# XMC4800-Power.net
KiCad netlist of a schematic drawn in Altium Designer
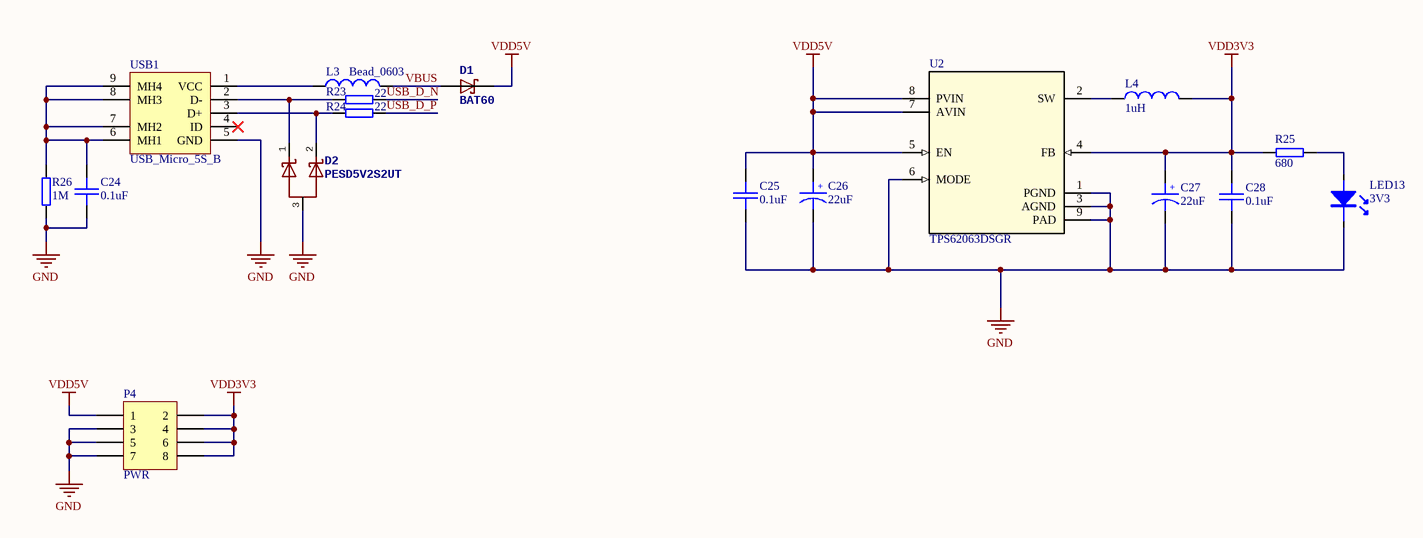
[diagram p0: XMC4800-Power.SchDoc]

(export (version "E")
  (design (tool "Eeschema 10.0.6"))
  (components
    (comp (ref "C24")
      (value "0.1uF")
      (footprint "CAP-0603")
      (description "陶瓷贴片电容0603")
      (fields (field (name "TOLERANCE") "10%") (field (name "VOLTAGE") "50V"))
      (libsource (lib "momo") (part "C_0603"))
    )
    (comp (ref "C25")
      (value "0.1uF")
      (footprint "CAP-0603")
      (description "陶瓷贴片电容0603")
      (fields (field (name "TOLERANCE") "10%") (field (name "VOLTAGE") "50V"))
      (libsource (lib "momo") (part "C_0603"))
    )
    (comp (ref "C26")
      (value "22uF")
      (footprint "C_Tantalum_B")
      (description "贴片钽电容B型")
      (fields (field (name "VOLTAGE") "16V"))
      (libsource (lib "momo") (part "C_Tantalum_B"))
    )
    (comp (ref "C27")
      (value "22uF")
      (footprint "C_Tantalum_B")
      (description "贴片钽电容B型")
      (fields (field (name "VOLTAGE") "16V"))
      (libsource (lib "momo") (part "C_Tantalum_B"))
    )
    (comp (ref "C28")
      (value "0.1uF")
      (footprint "CAP-0603")
      (description "陶瓷贴片电容0603")
      (fields (field (name "TOLERANCE") "10%") (field (name "VOLTAGE") "50V"))
      (libsource (lib "momo") (part "C_0603"))
    )
    (comp (ref "D1")
      (value "BAT60")
      (footprint "LC-SOD-323")
      (description "肖特基二极管")
      (libsource (lib "momo") (part "BAT60"))
    )
    (comp (ref "D2")
      (value "PESD5V2S2UT")
      (footprint "LC-SOT-23-3")
      (libsource (lib "momo") (part "PESD5V2S2UT"))
    )
    (comp (ref "L3")
      (value "Bead_0603")
      (footprint "L-0603")
      (description "贴片磁珠0603")
      (libsource (lib "momo") (part "Bead_0603"))
    )
    (comp (ref "L4")
      (value "1uH")
      (footprint "L-PWR-06030")
      (description "功率电感")
      (fields (field (name "TOLERANCE") "20%"))
      (libsource (lib "momo") (part "L_Power"))
    )
    (comp (ref "LED13")
      (value "3V3")
      (footprint "LED_0603")
      (description "0603封装发光二极管")
      (libsource (lib "momo") (part "LED_0603"))
    )
    (comp (ref "P4")
      (value "PWR")
      (footprint "HDR2X4")
      (description "Header, 4-Pin, Dual row")
      (fields (field (name "PUBLISHER") "Altium Limited"))
      (libsource (lib "Miscellaneous Connectors") (part "Header 4X2"))
    )
    (comp (ref "R23")
      (value "22")
      (footprint "RES-0603")
      (description "贴片电阻0603")
      (fields (field (name "TOLERANCE") "5%") (field (name "VOLTAGE") "50V"))
      (libsource (lib "momo") (part "R_0603"))
    )
    (comp (ref "R24")
      (value "22")
      (footprint "RES-0603")
      (description "贴片电阻0603")
      (fields (field (name "TOLERANCE") "5%") (field (name "VOLTAGE") "50V"))
      (libsource (lib "momo") (part "R_0603"))
    )
    (comp (ref "R25")
      (value "680")
      (footprint "RES-0603")
      (description "贴片电阻0603")
      (fields (field (name "TOLERANCE") "5%") (field (name "VOLTAGE") "50V"))
      (libsource (lib "momo") (part "R_0603"))
    )
    (comp (ref "R26")
      (value "1M")
      (footprint "RES-0603")
      (description "贴片电阻0603")
      (fields (field (name "TOLERANCE") "5%") (field (name "VOLTAGE") "50V"))
      (libsource (lib "momo") (part "R_0603"))
    )
    (comp (ref "U2")
      (value "TPS62063DSGR")
      (footprint "DSG0008A")
      (fields (field (name "PARTNUMBER") "TPS62063DSG") (field (name "MANUFACTURER") "Texas Instruments"))
      (libsource (lib "momo") (part "TPS62063DSGR"))
    )
    (comp (ref "USB1")
      (value "USB_Micro_5S_B")
      (footprint "USB_MICRO_5S_B")
      (description "micro USB母座5SB型")
      (libsource (lib "momo") (part "USB_Micro_5S_B"))
    )
  )
  (nets
    (net (code "1") (name "/USB_D_N") (class "Default")
      (node (ref "R23") (pin "2") (pinfunction "2_2") (pintype "passive"))
    )
    (net (code "2") (name "/USB_D_P") (class "Default")
      (node (ref "R24") (pin "2") (pinfunction "2_2") (pintype "passive"))
    )
    (net (code "3") (name "/VBUS") (class "Default")
      (node (ref "D1") (pin "1") (pinfunction "A_1") (pintype "passive"))
      (node (ref "L3") (pin "2") (pinfunction "2_2") (pintype "passive"))
    )
    (net (code "4") (name "GND") (class "Default")
      (node (ref "C24") (pin "2") (pinfunction "2_2") (pintype "passive"))
      (node (ref "C25") (pin "2") (pinfunction "2_2") (pintype "passive"))
      (node (ref "C26") (pin "2") (pinfunction "2_2") (pintype "passive"))
      (node (ref "C27") (pin "2") (pinfunction "2_2") (pintype "passive"))
      (node (ref "C28") (pin "2") (pinfunction "2_2") (pintype "passive"))
      (node (ref "D2") (pin "3") (pinfunction "3_3") (pintype "passive"))
      (node (ref "LED13") (pin "2") (pinfunction "K_2") (pintype "passive"))
      (node (ref "P4") (pin "3") (pinfunction "3_3") (pintype "passive"))
      (node (ref "P4") (pin "5") (pinfunction "5_5") (pintype "passive"))
      (node (ref "P4") (pin "7") (pinfunction "7_7") (pintype "passive"))
      (node (ref "R26") (pin "1") (pinfunction "1_1") (pintype "passive"))
      (node (ref "U2") (pin "1") (pinfunction "PGND_1") (pintype "power_in"))
      (node (ref "U2") (pin "3") (pinfunction "AGND_3") (pintype "power_in"))
      (node (ref "U2") (pin "6") (pinfunction "MODE_6") (pintype "input"))
      (node (ref "U2") (pin "9") (pinfunction "PAD_9") (pintype "power_in"))
      (node (ref "USB1") (pin "5") (pinfunction "GND_5") (pintype "power_in"))
    )
    (net (code "5") (name "Net-(LED13-A)") (class "Default")
      (node (ref "LED13") (pin "1") (pinfunction "A_1") (pintype "passive"))
      (node (ref "R25") (pin "2") (pinfunction "2_2") (pintype "passive"))
    )
    (net (code "6") (name "Net-(U2-SW)") (class "Default")
      (node (ref "L4") (pin "1") (pinfunction "1_1") (pintype "passive"))
      (node (ref "U2") (pin "2") (pinfunction "SW_2") (pintype "power_in"))
    )
    (net (code "7") (name "Net-(USB1-D+)") (class "Default")
      (node (ref "D2") (pin "2") (pinfunction "2_2") (pintype "passive"))
      (node (ref "R24") (pin "1") (pinfunction "1_1") (pintype "passive"))
      (node (ref "USB1") (pin "3") (pinfunction "D+_3") (pintype "passive"))
    )
    (net (code "8") (name "Net-(USB1-D-)") (class "Default")
      (node (ref "D2") (pin "1") (pinfunction "1_1") (pintype "passive"))
      (node (ref "R23") (pin "1") (pinfunction "1_1") (pintype "passive"))
      (node (ref "USB1") (pin "2") (pinfunction "D-_2") (pintype "passive"))
    )
    (net (code "9") (name "Net-(USB1-MH1)") (class "Default")
      (node (ref "C24") (pin "1") (pinfunction "1_1") (pintype "passive"))
      (node (ref "R26") (pin "2") (pinfunction "2_2") (pintype "passive"))
      (node (ref "USB1") (pin "6") (pinfunction "MH1_6") (pintype "passive"))
      (node (ref "USB1") (pin "7") (pinfunction "MH2_7") (pintype "passive"))
      (node (ref "USB1") (pin "8") (pinfunction "MH3_8") (pintype "passive"))
      (node (ref "USB1") (pin "9") (pinfunction "MH4_9") (pintype "passive"))
    )
    (net (code "10") (name "Net-(USB1-VCC)") (class "Default")
      (node (ref "L3") (pin "1") (pinfunction "1_1") (pintype "passive"))
      (node (ref "USB1") (pin "1") (pinfunction "VCC_1") (pintype "power_in"))
    )
    (net (code "11") (name "VDD3V3") (class "Default")
      (node (ref "C27") (pin "1") (pinfunction "1_1") (pintype "passive"))
      (node (ref "C28") (pin "1") (pinfunction "1_1") (pintype "passive"))
      (node (ref "L4") (pin "2") (pinfunction "2_2") (pintype "passive"))
      (node (ref "P4") (pin "2") (pinfunction "2_2") (pintype "passive"))
      (node (ref "P4") (pin "4") (pinfunction "4_4") (pintype "passive"))
      (node (ref "P4") (pin "6") (pinfunction "6_6") (pintype "passive"))
      (node (ref "P4") (pin "8") (pinfunction "8_8") (pintype "passive"))
      (node (ref "R25") (pin "1") (pinfunction "1_1") (pintype "passive"))
      (node (ref "U2") (pin "4") (pinfunction "FB_4") (pintype "input"))
    )
    (net (code "12") (name "VDD5V") (class "Default")
      (node (ref "C25") (pin "1") (pinfunction "1_1") (pintype "passive"))
      (node (ref "C26") (pin "1") (pinfunction "1_1") (pintype "passive"))
      (node (ref "D1") (pin "2") (pinfunction "C_2") (pintype "passive"))
      (node (ref "P4") (pin "1") (pinfunction "1_1") (pintype "passive"))
      (node (ref "U2") (pin "5") (pinfunction "EN_5") (pintype "input"))
      (node (ref "U2") (pin "7") (pinfunction "AVIN_7") (pintype "power_in"))
      (node (ref "U2") (pin "8") (pinfunction "PVIN_8") (pintype "power_in"))
    )
    (net (code "13") (name "unconnected-(USB1-ID-Pad4)") (class "Default")
      (node (ref "USB1") (pin "4") (pinfunction "ID_4") (pintype "passive+no_connect"))
    )
  )
)
